# Long_Freq_to_Volt_Converter.net
KiCad netlist of a schematic drawn in Altium Designer
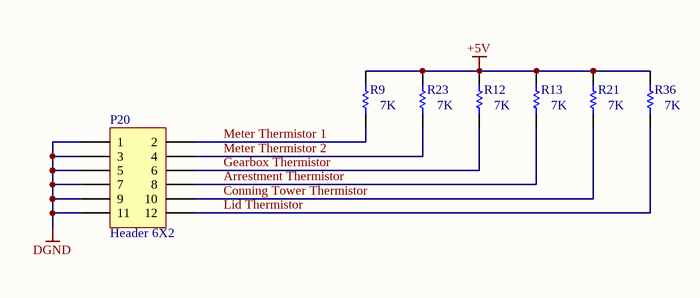
[diagram p0: Long Freq to Volt Converter.SchDoc]

(export (version "E")
  (design (tool "Eeschema 10.0.6"))
  (components
    (comp (ref "P20")
      (value "Header 6X2")
      (footprint "HDR2X6")
      (description "Header, 6-Pin, Dual row")
      (fields (field (name "PUBLISHER") "Altium Limited"))
      (libsource (lib "Miscellaneous Connectors") (part "Header 6X2"))
    )
    (comp (ref "R9")
      (value "7K")
      (footprint "AXIAL-0.3")
      (description "Resistor")
      (fields (field (name "Comment") "Res1") (field (name "PUBLISHER") "Altium Limited"))
      (libsource (lib "Miscellaneous Devices") (part "Res1"))
    )
    (comp (ref "R12")
      (value "7K")
      (footprint "AXIAL-0.3")
      (description "Resistor")
      (fields (field (name "Comment") "Res1") (field (name "PUBLISHER") "Altium Limited"))
      (libsource (lib "Miscellaneous Devices") (part "Res1"))
    )
    (comp (ref "R13")
      (value "7K")
      (footprint "AXIAL-0.3")
      (description "Resistor")
      (fields (field (name "Comment") "Res1") (field (name "PUBLISHER") "Altium Limited"))
      (libsource (lib "Miscellaneous Devices") (part "Res1"))
    )
    (comp (ref "R21")
      (value "7K")
      (footprint "AXIAL-0.3")
      (description "Resistor")
      (fields (field (name "Comment") "Res1") (field (name "PUBLISHER") "Altium Limited"))
      (libsource (lib "Miscellaneous Devices") (part "Res1"))
    )
    (comp (ref "R23")
      (value "7K")
      (footprint "AXIAL-0.3")
      (description "Resistor")
      (fields (field (name "Comment") "Res1") (field (name "PUBLISHER") "Altium Limited"))
      (libsource (lib "Miscellaneous Devices") (part "Res1"))
    )
    (comp (ref "R36")
      (value "7K")
      (footprint "AXIAL-0.3")
      (description "Resistor")
      (fields (field (name "Comment") "Res1") (field (name "PUBLISHER") "Altium Limited"))
      (libsource (lib "Miscellaneous Devices") (part "Res1"))
    )
  )
  (nets
    (net (code "1") (name "+5V") (class "Default")
      (node (ref "R12") (pin "2") (pinfunction "2_2") (pintype "passive"))
      (node (ref "R13") (pin "2") (pinfunction "2_2") (pintype "passive"))
      (node (ref "R21") (pin "2") (pinfunction "2_2") (pintype "passive"))
      (node (ref "R23") (pin "2") (pinfunction "2_2") (pintype "passive"))
      (node (ref "R36") (pin "2") (pinfunction "2_2") (pintype "passive"))
      (node (ref "R9") (pin "2") (pinfunction "2_2") (pintype "passive"))
    )
    (net (code "2") (name "/Arrestment Thermistor") (class "Default")
      (node (ref "P20") (pin "8") (pinfunction "8_8") (pintype "passive"))
      (node (ref "R13") (pin "1") (pinfunction "1_1") (pintype "passive"))
    )
    (net (code "3") (name "/Conning Tower Thermistor") (class "Default")
      (node (ref "P20") (pin "10") (pinfunction "10_10") (pintype "passive"))
      (node (ref "R21") (pin "1") (pinfunction "1_1") (pintype "passive"))
    )
    (net (code "4") (name "/Gearbox Thermistor") (class "Default")
      (node (ref "P20") (pin "6") (pinfunction "6_6") (pintype "passive"))
      (node (ref "R12") (pin "1") (pinfunction "1_1") (pintype "passive"))
    )
    (net (code "5") (name "/Lid Thermistor") (class "Default")
      (node (ref "P20") (pin "12") (pinfunction "12_12") (pintype "passive"))
      (node (ref "R36") (pin "1") (pinfunction "1_1") (pintype "passive"))
    )
    (net (code "6") (name "/Meter Thermistor 1") (class "Default")
      (node (ref "P20") (pin "2") (pinfunction "2_2") (pintype "passive"))
      (node (ref "R9") (pin "1") (pinfunction "1_1") (pintype "passive"))
    )
    (net (code "7") (name "/Meter Thermistor 2") (class "Default")
      (node (ref "P20") (pin "4") (pinfunction "4_4") (pintype "passive"))
      (node (ref "R23") (pin "1") (pinfunction "1_1") (pintype "passive"))
    )
    (net (code "8") (name "DGND") (class "Default")
      (node (ref "P20") (pin "1") (pinfunction "1_1") (pintype "passive"))
      (node (ref "P20") (pin "11") (pinfunction "11_11") (pintype "passive"))
      (node (ref "P20") (pin "3") (pinfunction "3_3") (pintype "passive"))
      (node (ref "P20") (pin "5") (pinfunction "5_5") (pintype "passive"))
      (node (ref "P20") (pin "7") (pinfunction "7_7") (pintype "passive"))
      (node (ref "P20") (pin "9") (pinfunction "9_9") (pintype "passive"))
    )
  )
)
